# Oscar_MainBoard_Power.net
KiCad netlist of a schematic drawn in Altium Designer
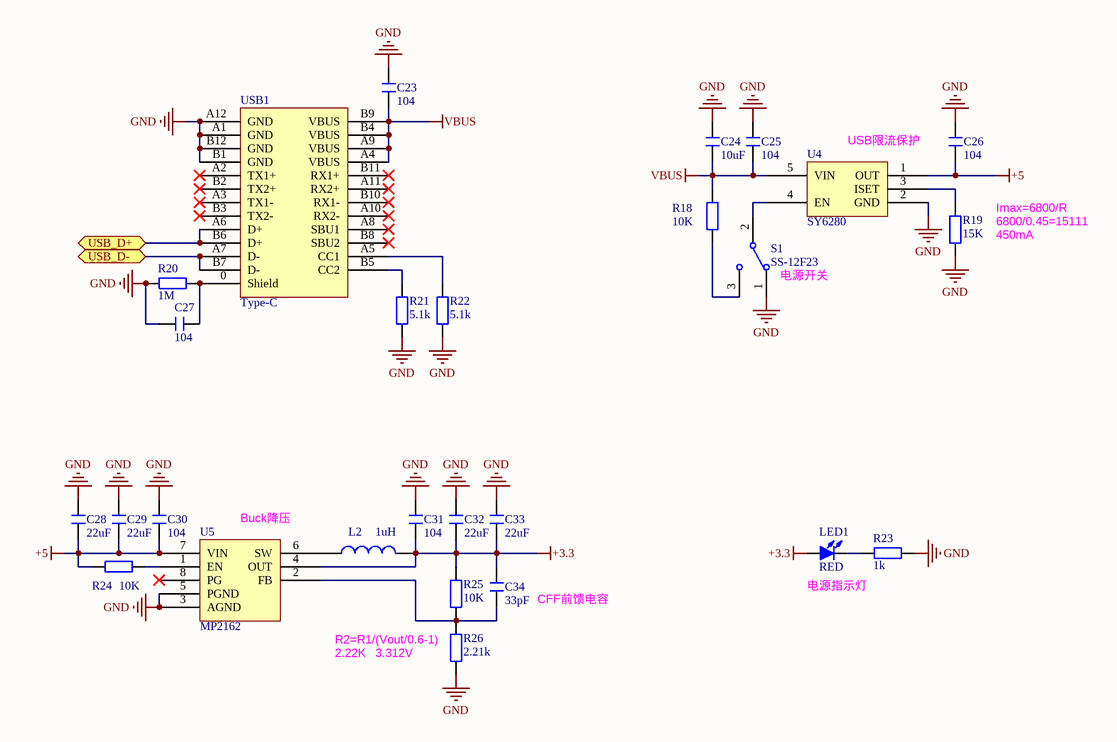
[diagram p0: Oscar_MainBoard_Power.SchDoc]

(export (version "E")
  (design (tool "Eeschema 10.0.6"))
  (components
    (comp (ref "C23")
      (value "104")
      (footprint "C 0402_L")
      (description "贴片电容")
      (libsource (lib "0.1 - 电阻-电容-电感") (part "C"))
    )
    (comp (ref "C24")
      (value "10uF")
      (footprint "C 0603_L")
      (description "贴片电容")
      (libsource (lib "0.1 - 电阻-电容-电感") (part "C"))
    )
    (comp (ref "C25")
      (value "104")
      (footprint "C 0402_L")
      (description "贴片电容")
      (libsource (lib "0.1 - 电阻-电容-电感") (part "C"))
    )
    (comp (ref "C26")
      (value "104")
      (footprint "C 0402_L")
      (description "贴片电容")
      (libsource (lib "0.1 - 电阻-电容-电感") (part "C"))
    )
    (comp (ref "C27")
      (value "104")
      (footprint "C 0402_L")
      (description "贴片电容")
      (libsource (lib "0.1 - 电阻-电容-电感") (part "C"))
    )
    (comp (ref "C28")
      (value "22uF")
      (footprint "C 0805_L")
      (description "贴片电容")
      (libsource (lib "0.1 - 电阻-电容-电感") (part "C"))
    )
    (comp (ref "C29")
      (value "22uF")
      (footprint "C 0805_L")
      (description "贴片电容")
      (libsource (lib "0.1 - 电阻-电容-电感") (part "C"))
    )
    (comp (ref "C30")
      (value "104")
      (footprint "C 0402_L")
      (description "贴片电容")
      (libsource (lib "0.1 - 电阻-电容-电感") (part "C"))
    )
    (comp (ref "C31")
      (value "104")
      (footprint "C 0402_L")
      (description "贴片电容")
      (libsource (lib "0.1 - 电阻-电容-电感") (part "C"))
    )
    (comp (ref "C32")
      (value "22uF")
      (footprint "C 0805_L")
      (description "贴片电容")
      (libsource (lib "0.1 - 电阻-电容-电感") (part "C"))
    )
    (comp (ref "C33")
      (value "22uF")
      (footprint "C 0805_L")
      (description "贴片电容")
      (libsource (lib "0.1 - 电阻-电容-电感") (part "C"))
    )
    (comp (ref "C34")
      (value "33pF")
      (footprint "C 0402_L")
      (description "贴片电容")
      (libsource (lib "0.1 - 电阻-电容-电感") (part "C"))
    )
    (comp (ref "L2")
      (value "1uH")
      (footprint "CD32")
      (description "小功率贴片电感")
      (libsource (lib "0.1 - 电阻-电容-电感") (part "L"))
    )
    (comp (ref "LED1")
      (value "RED")
      (footprint "LED_0603")
      (description "贴片LED")
      (libsource (lib "0.3 - LED发光二极管") (part "LED-SMD"))
    )
    (comp (ref "R18")
      (value "10K")
      (footprint "R 0402_L")
      (description "贴片电阻")
      (libsource (lib "0.1 - 电阻-电容-电感") (part "R"))
    )
    (comp (ref "R19")
      (value "15K")
      (footprint "R 0402_L")
      (description "贴片电阻")
      (libsource (lib "0.1 - 电阻-电容-电感") (part "R"))
    )
    (comp (ref "R20")
      (value "1M")
      (footprint "R 0402_L")
      (description "贴片电阻")
      (libsource (lib "0.1 - 电阻-电容-电感") (part "R"))
    )
    (comp (ref "R21")
      (value "5.1k")
      (footprint "R 0402_L")
      (description "贴片电阻")
      (libsource (lib "0.1 - 电阻-电容-电感") (part "R"))
    )
    (comp (ref "R22")
      (value "5.1k")
      (footprint "R 0402_L")
      (description "贴片电阻")
      (libsource (lib "0.1 - 电阻-电容-电感") (part "R"))
    )
    (comp (ref "R23")
      (value "1k")
      (footprint "R 0402_L")
      (description "贴片电阻")
      (libsource (lib "0.1 - 电阻-电容-电感") (part "R"))
    )
    (comp (ref "R24")
      (value "10K")
      (footprint "R 0402_L")
      (description "贴片电阻")
      (libsource (lib "0.1 - 电阻-电容-电感") (part "R"))
    )
    (comp (ref "R25")
      (value "10K")
      (footprint "R 0402_L")
      (description "贴片电阻")
      (libsource (lib "0.1 - 电阻-电容-电感") (part "R"))
    )
    (comp (ref "R26")
      (value "2.21k")
      (footprint "R 0402_L")
      (description "贴片电阻")
      (libsource (lib "0.1 - 电阻-电容-电感") (part "R"))
    )
    (comp (ref "S1")
      (value "SS-12F23")
      (footprint "MSK-12C01-07")
      (description "1路波动开关")
      (fields (field (name "版权归属") "封装库来自淘宝 ID：黄晶宝石"))
      (libsource (lib "0.7 - 常用按键-开关-蜂鸣器-电池") (part "SSW-1P"))
    )
    (comp (ref "U4")
      (value "SY6280")
      (footprint "SOT23-5N")
      (description "电源限流保护芯片")
      (libsource (lib "1.1 - 电源类芯片") (part "SY6280"))
    )
    (comp (ref "U5")
      (value "MP2162")
      (footprint "QFN8")
      (description "2.5-6v 2A buck IC")
      (libsource (lib "1.1 - 电源类芯片") (part "MP2162"))
    )
    (comp (ref "USB1")
      (value "Type-C")
      (footprint "USB-TYPE-C_16PIN-MALE-TYPE-C-31-M-12")
      (libsource (lib "type-c") (part "Type-C"))
    )
  )
  (nets
    (net (code "1") (name "+3.3") (class "Default")
      (node (ref "C31") (pin "1") (pinfunction "1_1") (pintype "passive"))
      (node (ref "C32") (pin "1") (pinfunction "1_1") (pintype "passive"))
      (node (ref "C33") (pin "1") (pinfunction "1_1") (pintype "passive"))
      (node (ref "C34") (pin "2") (pinfunction "2_2") (pintype "passive"))
      (node (ref "L2") (pin "2") (pinfunction "2_2") (pintype "passive"))
      (node (ref "LED1") (pin "1") (pinfunction "A_1") (pintype "passive"))
      (node (ref "R25") (pin "1") (pinfunction "1_1") (pintype "passive"))
      (node (ref "U5") (pin "4") (pinfunction "OUT_4") (pintype "passive"))
    )
    (net (code "2") (name "+5") (class "Default")
      (node (ref "C26") (pin "1") (pinfunction "1_1") (pintype "passive"))
      (node (ref "C28") (pin "1") (pinfunction "1_1") (pintype "passive"))
      (node (ref "C29") (pin "1") (pinfunction "1_1") (pintype "passive"))
      (node (ref "C30") (pin "1") (pinfunction "1_1") (pintype "passive"))
      (node (ref "R24") (pin "1") (pinfunction "1_1") (pintype "passive"))
      (node (ref "U4") (pin "1") (pinfunction "OUT_1") (pintype "passive"))
      (node (ref "U5") (pin "7") (pinfunction "VIN_7") (pintype "passive"))
    )
    (net (code "3") (name "/USB_D+") (class "Default")
      (node (ref "USB1") (pin "A6") (pinfunction "D+_A6") (pintype "passive"))
      (node (ref "USB1") (pin "B6") (pinfunction "D+_B6") (pintype "passive"))
    )
    (net (code "4") (name "/USB_D-") (class "Default")
      (node (ref "USB1") (pin "A7") (pinfunction "D-_A7") (pintype "passive"))
      (node (ref "USB1") (pin "B7") (pinfunction "D-_B7") (pintype "passive"))
    )
    (net (code "5") (name "GND") (class "Default")
      (node (ref "C23") (pin "2") (pinfunction "2_2") (pintype "passive"))
      (node (ref "C24") (pin "2") (pinfunction "2_2") (pintype "passive"))
      (node (ref "C25") (pin "2") (pinfunction "2_2") (pintype "passive"))
      (node (ref "C26") (pin "2") (pinfunction "2_2") (pintype "passive"))
      (node (ref "C27") (pin "2") (pinfunction "2_2") (pintype "passive"))
      (node (ref "C28") (pin "2") (pinfunction "2_2") (pintype "passive"))
      (node (ref "C29") (pin "2") (pinfunction "2_2") (pintype "passive"))
      (node (ref "C30") (pin "2") (pinfunction "2_2") (pintype "passive"))
      (node (ref "C31") (pin "2") (pinfunction "2_2") (pintype "passive"))
      (node (ref "C32") (pin "2") (pinfunction "2_2") (pintype "passive"))
      (node (ref "C33") (pin "2") (pinfunction "2_2") (pintype "passive"))
      (node (ref "R19") (pin "2") (pinfunction "2_2") (pintype "passive"))
      (node (ref "R20") (pin "2") (pinfunction "2_2") (pintype "passive"))
      (node (ref "R21") (pin "1") (pinfunction "1_1") (pintype "passive"))
      (node (ref "R22") (pin "1") (pinfunction "1_1") (pintype "passive"))
      (node (ref "R23") (pin "2") (pinfunction "2_2") (pintype "passive"))
      (node (ref "R26") (pin "2") (pinfunction "2_2") (pintype "passive"))
      (node (ref "S1") (pin "1") (pinfunction "1_1") (pintype "passive"))
      (node (ref "U4") (pin "2") (pinfunction "GND_2") (pintype "passive"))
      (node (ref "U5") (pin "3") (pinfunction "AGND_3") (pintype "passive"))
      (node (ref "U5") (pin "5") (pinfunction "PGND_5") (pintype "passive"))
      (node (ref "USB1") (pin "A1") (pinfunction "GND_A1") (pintype "passive"))
      (node (ref "USB1") (pin "A12") (pinfunction "GND_A12") (pintype "passive"))
      (node (ref "USB1") (pin "B1") (pinfunction "GND_B1") (pintype "passive"))
      (node (ref "USB1") (pin "B12") (pinfunction "GND_B12") (pintype "passive"))
    )
    (net (code "6") (name "Net-(LED1-K)") (class "Default")
      (node (ref "LED1") (pin "2") (pinfunction "K_2") (pintype "passive"))
      (node (ref "R23") (pin "1") (pinfunction "1_1") (pintype "passive"))
    )
    (net (code "7") (name "Net-(R18-Pad2)") (class "Default")
      (node (ref "R18") (pin "2") (pinfunction "2_2") (pintype "passive"))
      (node (ref "S1") (pin "3") (pinfunction "3_3") (pintype "passive"))
    )
    (net (code "8") (name "Net-(U4-EN)") (class "Default")
      (node (ref "S1") (pin "2") (pinfunction "2_2") (pintype "passive"))
      (node (ref "U4") (pin "4") (pinfunction "EN_4") (pintype "passive"))
    )
    (net (code "9") (name "Net-(U4-ISET)") (class "Default")
      (node (ref "R19") (pin "1") (pinfunction "1_1") (pintype "passive"))
      (node (ref "U4") (pin "3") (pinfunction "ISET_3") (pintype "passive"))
    )
    (net (code "10") (name "Net-(U5-EN)") (class "Default")
      (node (ref "R24") (pin "2") (pinfunction "2_2") (pintype "passive"))
      (node (ref "U5") (pin "1") (pinfunction "EN_1") (pintype "passive"))
    )
    (net (code "11") (name "Net-(U5-FB)") (class "Default")
      (node (ref "C34") (pin "1") (pinfunction "1_1") (pintype "passive"))
      (node (ref "R25") (pin "2") (pinfunction "2_2") (pintype "passive"))
      (node (ref "R26") (pin "1") (pinfunction "1_1") (pintype "passive"))
      (node (ref "U5") (pin "2") (pinfunction "FB_2") (pintype "passive"))
    )
    (net (code "12") (name "Net-(U5-SW)") (class "Default")
      (node (ref "L2") (pin "1") (pinfunction "1_1") (pintype "passive"))
      (node (ref "U5") (pin "6") (pinfunction "SW_6") (pintype "passive"))
    )
    (net (code "13") (name "Net-(USB1-CC1)") (class "Default")
      (node (ref "R22") (pin "2") (pinfunction "2_2") (pintype "passive"))
      (node (ref "USB1") (pin "A5") (pinfunction "CC1_A5") (pintype "passive"))
    )
    (net (code "14") (name "Net-(USB1-CC2)") (class "Default")
      (node (ref "R21") (pin "2") (pinfunction "2_2") (pintype "passive"))
      (node (ref "USB1") (pin "B5") (pinfunction "CC2_B5") (pintype "passive"))
    )
    (net (code "15") (name "Net-(USB1-Shield)") (class "Default")
      (node (ref "C27") (pin "1") (pinfunction "1_1") (pintype "passive"))
      (node (ref "R20") (pin "1") (pinfunction "1_1") (pintype "passive"))
      (node (ref "USB1") (pin "0") (pinfunction "Shield_0") (pintype "passive"))
    )
    (net (code "16") (name "VBUS") (class "Default")
      (node (ref "C23") (pin "1") (pinfunction "1_1") (pintype "passive"))
      (node (ref "C24") (pin "1") (pinfunction "1_1") (pintype "passive"))
      (node (ref "C25") (pin "1") (pinfunction "1_1") (pintype "passive"))
      (node (ref "R18") (pin "1") (pinfunction "1_1") (pintype "passive"))
      (node (ref "U4") (pin "5") (pinfunction "VIN_5") (pintype "passive"))
      (node (ref "USB1") (pin "A4") (pinfunction "VBUS_A4") (pintype "passive"))
      (node (ref "USB1") (pin "A9") (pinfunction "VBUS_A9") (pintype "passive"))
      (node (ref "USB1") (pin "B4") (pinfunction "VBUS_B4") (pintype "passive"))
      (node (ref "USB1") (pin "B9") (pinfunction "VBUS_B9") (pintype "passive"))
    )
    (net (code "17") (name "unconnected-(U5-PG-Pad8)") (class "Default")
      (node (ref "U5") (pin "8") (pinfunction "PG_8") (pintype "passive+no_connect"))
    )
    (net (code "18") (name "unconnected-(USB1-RX1+-PadB11)") (class "Default")
      (node (ref "USB1") (pin "B11") (pinfunction "RX1+_B11") (pintype "passive+no_connect"))
    )
    (net (code "19") (name "unconnected-(USB1-RX1--PadB10)") (class "Default")
      (node (ref "USB1") (pin "B10") (pinfunction "RX1-_B10") (pintype "passive+no_connect"))
    )
    (net (code "20") (name "unconnected-(USB1-RX2+-PadA11)") (class "Default")
      (node (ref "USB1") (pin "A11") (pinfunction "RX2+_A11") (pintype "passive+no_connect"))
    )
    (net (code "21") (name "unconnected-(USB1-RX2--PadA10)") (class "Default")
      (node (ref "USB1") (pin "A10") (pinfunction "RX2-_A10") (pintype "passive+no_connect"))
    )
    (net (code "22") (name "unconnected-(USB1-SBU1-PadA8)") (class "Default")
      (node (ref "USB1") (pin "A8") (pinfunction "SBU1_A8") (pintype "passive+no_connect"))
    )
    (net (code "23") (name "unconnected-(USB1-SBU2-PadB8)") (class "Default")
      (node (ref "USB1") (pin "B8") (pinfunction "SBU2_B8") (pintype "passive+no_connect"))
    )
    (net (code "24") (name "unconnected-(USB1-TX1+-PadA2)") (class "Default")
      (node (ref "USB1") (pin "A2") (pinfunction "TX1+_A2") (pintype "passive+no_connect"))
    )
    (net (code "25") (name "unconnected-(USB1-TX1--PadA3)") (class "Default")
      (node (ref "USB1") (pin "A3") (pinfunction "TX1-_A3") (pintype "passive+no_connect"))
    )
    (net (code "26") (name "unconnected-(USB1-TX2+-PadB2)") (class "Default")
      (node (ref "USB1") (pin "B2") (pinfunction "TX2+_B2") (pintype "passive+no_connect"))
    )
    (net (code "27") (name "unconnected-(USB1-TX2--PadB3)") (class "Default")
      (node (ref "USB1") (pin "B3") (pinfunction "TX2-_B3") (pintype "passive+no_connect"))
    )
  )
)
